# EL3.net
KiCad netlist of a schematic drawn in EAGLE
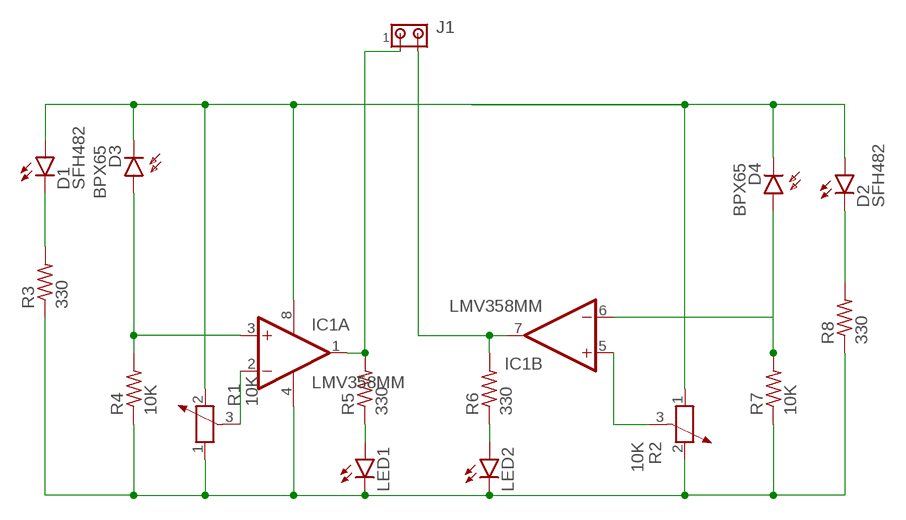
[diagram p0: schematic, sheet 1]

(export (version "E")
  (design (tool "Eeschema 10.0.6"))
  (components
    (comp (ref "D1")
      (value "SFH482")
      (footprint "eagle-import:SFH482")
      (libsource (lib "eagle-import") (part "SFH482"))
    )
    (comp (ref "D2")
      (value "SFH482")
      (footprint "eagle-import:SFH482")
      (libsource (lib "eagle-import") (part "SFH482"))
    )
    (comp (ref "D3")
      (value "BPX65")
      (footprint "eagle-import:BPX65")
      (fields (field (name "MPN") "BPX65."))
      (libsource (lib "eagle-import") (part "BPX65"))
    )
    (comp (ref "D4")
      (value "BPX65")
      (footprint "eagle-import:BPX65")
      (fields (field (name "MPN") "BPX65."))
      (libsource (lib "eagle-import") (part "BPX65"))
    )
    (comp (ref "IC1")
      (value "LMV358MM")
      (footprint "eagle-import:MSOP08")
      (libsource (lib "eagle-import") (part "LMV358?MM"))
    )
    (comp (ref "J1")
      (value "MTA02-100")
      (footprint "eagle-import:10X02MTA")
      (libsource (lib "eagle-import") (part "MTA02-100"))
    )
    (comp (ref "LED1")
      (value "LED3MM")
      (footprint "eagle-import:LED3MM")
      (libsource (lib "eagle-import") (part "LED3MM"))
    )
    (comp (ref "LED2")
      (value "LED3MM")
      (footprint "eagle-import:LED3MM")
      (libsource (lib "eagle-import") (part "LED3MM"))
    )
    (comp (ref "R1")
      (value "10K")
      (footprint "eagle-import:PT-10")
      (libsource (lib "eagle-import") (part "POTENTIOMETER_PT-10"))
    )
    (comp (ref "R2")
      (value "10K")
      (footprint "eagle-import:PT-10")
      (libsource (lib "eagle-import") (part "POTENTIOMETER_PT-10"))
    )
    (comp (ref "R3")
      (value "330")
      (footprint "eagle-import:0204_5")
      (libsource (lib "eagle-import") (part "R-US_0204/5"))
    )
    (comp (ref "R4")
      (value "10K")
      (footprint "eagle-import:0204_5")
      (libsource (lib "eagle-import") (part "R-US_0204/5"))
    )
    (comp (ref "R5")
      (value "330")
      (footprint "eagle-import:0204_5")
      (libsource (lib "eagle-import") (part "R-US_0204/5"))
    )
    (comp (ref "R6")
      (value "330")
      (footprint "eagle-import:0204_5")
      (libsource (lib "eagle-import") (part "R-US_0204/5"))
    )
    (comp (ref "R7")
      (value "10K")
      (footprint "eagle-import:0204_5")
      (libsource (lib "eagle-import") (part "R-US_0204/5"))
    )
    (comp (ref "R8")
      (value "330")
      (footprint "eagle-import:0204_5")
      (libsource (lib "eagle-import") (part "R-US_0204/5"))
    )
  )
  (nets
    (net (code "1") (name "Net-(D1-C)") (class "Default")
      (node (ref "D1") (pin "K") (pinfunction "C_K") (pintype "passive"))
      (node (ref "R3") (pin "2") (pinfunction "2_2") (pintype "passive"))
    )
    (net (code "2") (name "Net-(D2-C)") (class "Default")
      (node (ref "D2") (pin "K") (pinfunction "C_K") (pintype "passive"))
      (node (ref "R8") (pin "2") (pinfunction "2_2") (pintype "passive"))
    )
    (net (code "3") (name "Net-(D3-C)") (class "Default")
      (node (ref "D1") (pin "A") (pinfunction "A_A") (pintype "passive"))
      (node (ref "D2") (pin "A") (pinfunction "A_A") (pintype "passive"))
      (node (ref "D3") (pin "K") (pinfunction "C_K") (pintype "passive"))
      (node (ref "D4") (pin "K") (pinfunction "C_K") (pintype "passive"))
      (node (ref "IC1") (pin "8") (pinfunction "V+_8") (pintype "power_in"))
      (node (ref "R1") (pin "2") (pinfunction "2_2") (pintype "passive"))
      (node (ref "R2") (pin "1") (pinfunction "1_1") (pintype "passive"))
    )
    (net (code "4") (name "Net-(IC1A-+IN)") (class "Default")
      (node (ref "D3") (pin "A") (pinfunction "A_A") (pintype "passive"))
      (node (ref "IC1") (pin "3") (pinfunction "+IN_3") (pintype "input"))
      (node (ref "R4") (pin "2") (pinfunction "2_2") (pintype "passive"))
    )
    (net (code "5") (name "Net-(IC1A--IN)") (class "Default")
      (node (ref "IC1") (pin "2") (pinfunction "-IN_2") (pintype "input"))
      (node (ref "R1") (pin "3") (pinfunction "3_3") (pintype "passive"))
    )
    (net (code "6") (name "Net-(IC1A-OUT)") (class "Default")
      (node (ref "IC1") (pin "1") (pinfunction "OUT_1") (pintype "output"))
      (node (ref "J1") (pin "1") (pinfunction "1_1") (pintype "passive"))
      (node (ref "R5") (pin "2") (pinfunction "2_2") (pintype "passive"))
    )
    (net (code "7") (name "Net-(IC1B-+IN)") (class "Default")
      (node (ref "IC1") (pin "5") (pinfunction "+IN_5") (pintype "input"))
      (node (ref "R2") (pin "3") (pinfunction "3_3") (pintype "passive"))
    )
    (net (code "8") (name "Net-(IC1B--IN)") (class "Default")
      (node (ref "D4") (pin "A") (pinfunction "A_A") (pintype "passive"))
      (node (ref "IC1") (pin "6") (pinfunction "-IN_6") (pintype "input"))
      (node (ref "R7") (pin "2") (pinfunction "2_2") (pintype "passive"))
    )
    (net (code "9") (name "Net-(IC1B-OUT)") (class "Default")
      (node (ref "IC1") (pin "7") (pinfunction "OUT_7") (pintype "output"))
      (node (ref "J1") (pin "2") (pinfunction "2_2") (pintype "passive"))
      (node (ref "R6") (pin "2") (pinfunction "2_2") (pintype "passive"))
    )
    (net (code "10") (name "Net-(IC1C-V-)") (class "Default")
      (node (ref "IC1") (pin "4") (pinfunction "V-_4") (pintype "power_in"))
      (node (ref "LED1") (pin "K") (pinfunction "C_K") (pintype "passive"))
      (node (ref "LED2") (pin "K") (pinfunction "C_K") (pintype "passive"))
      (node (ref "R1") (pin "1") (pinfunction "1_1") (pintype "passive"))
      (node (ref "R2") (pin "2") (pinfunction "2_2") (pintype "passive"))
      (node (ref "R3") (pin "1") (pinfunction "1_1") (pintype "passive"))
      (node (ref "R4") (pin "1") (pinfunction "1_1") (pintype "passive"))
      (node (ref "R7") (pin "1") (pinfunction "1_1") (pintype "passive"))
      (node (ref "R8") (pin "1") (pinfunction "1_1") (pintype "passive"))
    )
    (net (code "11") (name "Net-(LED1-PadA)") (class "Default")
      (node (ref "LED1") (pin "A") (pinfunction "A_A") (pintype "passive"))
      (node (ref "R5") (pin "1") (pinfunction "1_1") (pintype "passive"))
    )
    (net (code "12") (name "Net-(LED2-PadA)") (class "Default")
      (node (ref "LED2") (pin "A") (pinfunction "A_A") (pintype "passive"))
      (node (ref "R6") (pin "1") (pinfunction "1_1") (pintype "passive"))
    )
  )
)
